# RemSw1_0.net
KiCad netlist of a schematic drawn in EAGLE
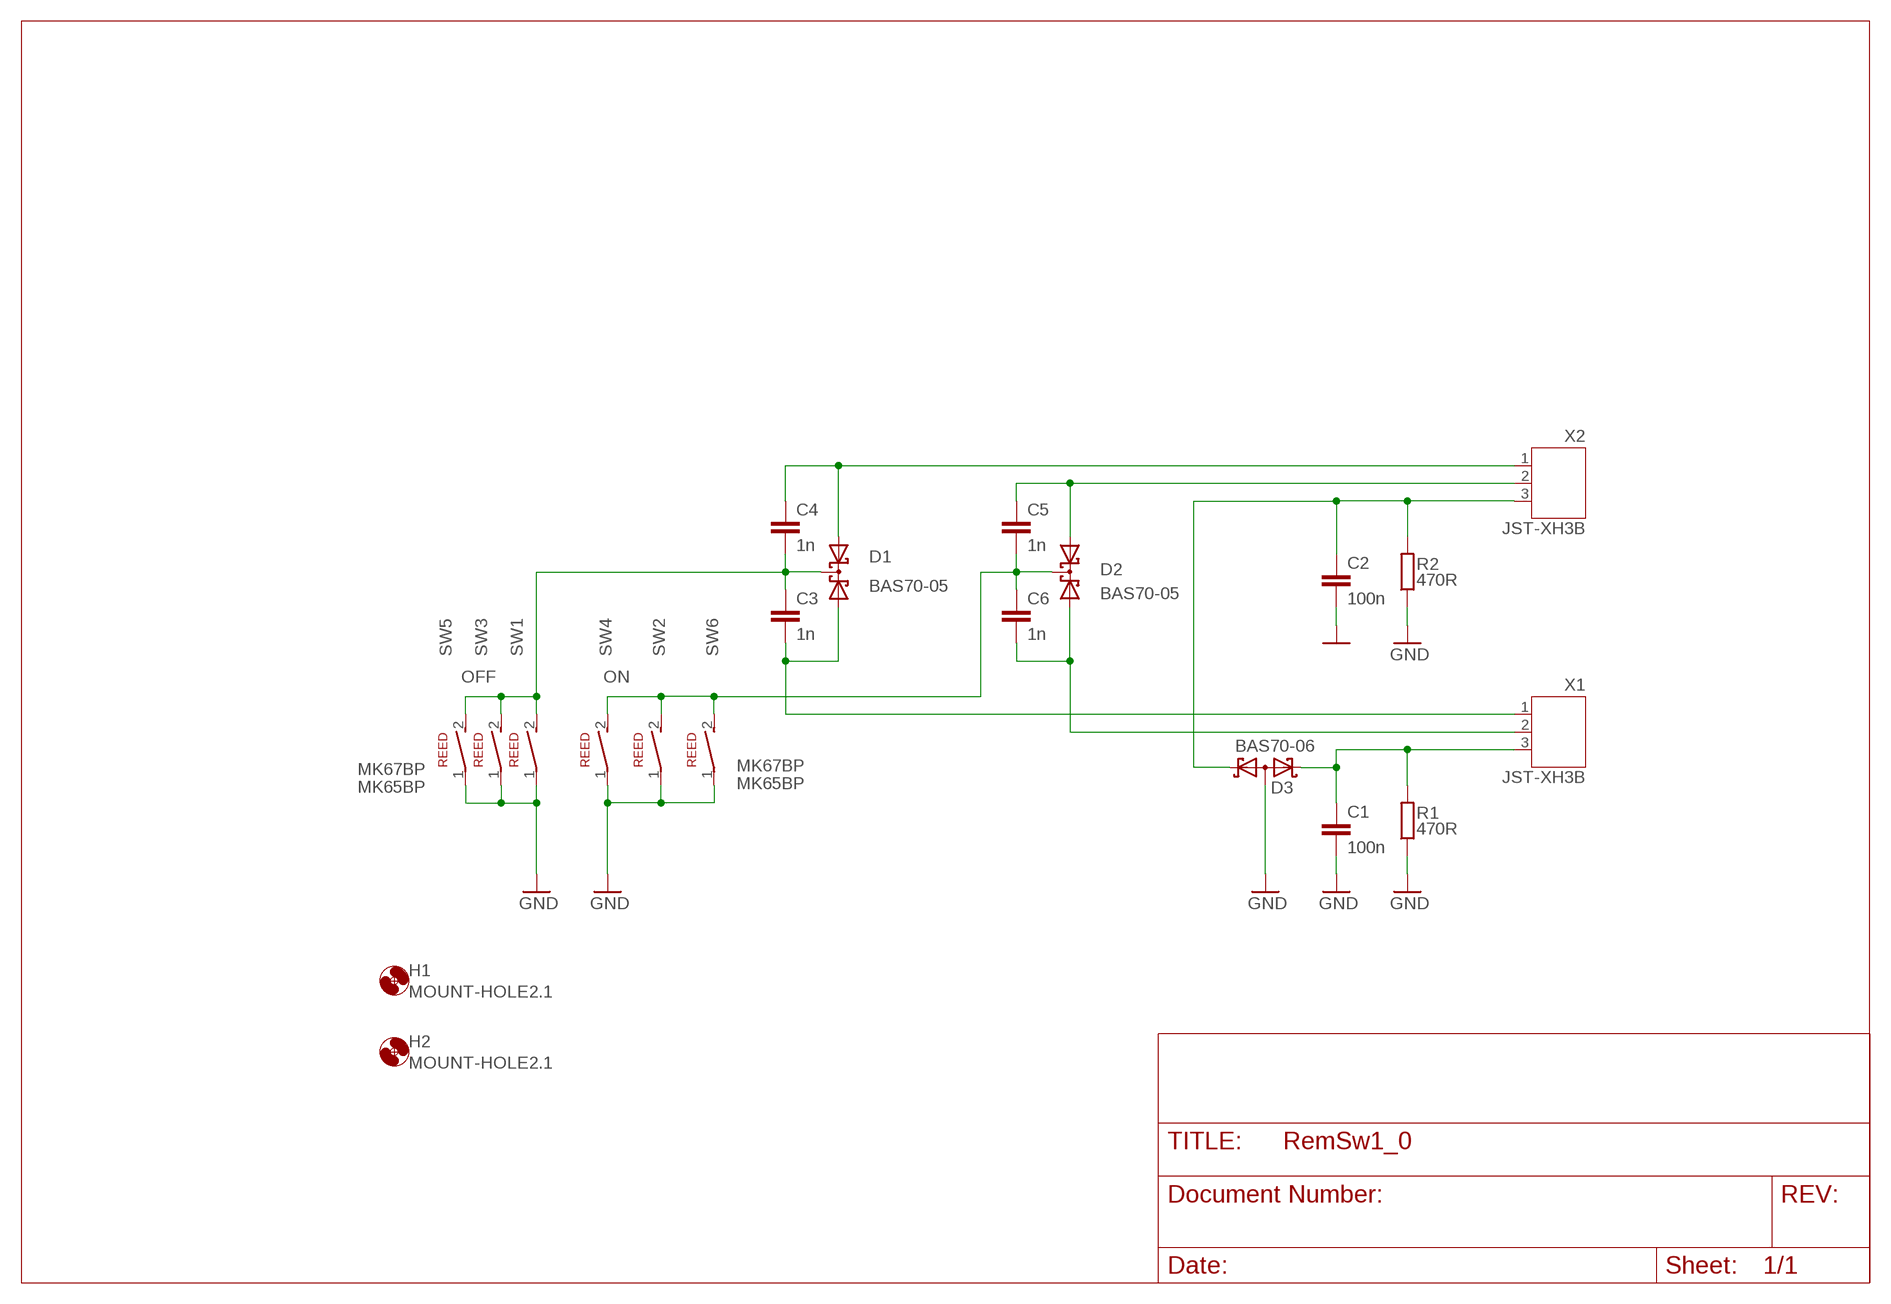
[diagram p0: schematic, sheet 1]

(export (version "E")
  (design (tool "Eeschema 10.0.6"))
  (components
    (comp (ref "C1")
      (value "100n")
      (footprint "eagle-import:C0805")
      (libsource (lib "eagle-import") (part "C-EUC0805"))
    )
    (comp (ref "C2")
      (value "100n")
      (footprint "eagle-import:C0805")
      (libsource (lib "eagle-import") (part "C-EUC0805"))
    )
    (comp (ref "C3")
      (value "1n")
      (footprint "eagle-import:C0805")
      (libsource (lib "eagle-import") (part "C-EUC0805"))
    )
    (comp (ref "C4")
      (value "1n")
      (footprint "eagle-import:C0805")
      (libsource (lib "eagle-import") (part "C-EUC0805"))
    )
    (comp (ref "C5")
      (value "1n")
      (footprint "eagle-import:C0805")
      (libsource (lib "eagle-import") (part "C-EUC0805"))
    )
    (comp (ref "C6")
      (value "1n")
      (footprint "eagle-import:C0805")
      (libsource (lib "eagle-import") (part "C-EUC0805"))
    )
    (comp (ref "D1")
      (value "BAS70-05")
      (footprint "eagle-import:SOT23")
      (libsource (lib "eagle-import") (part "BAS70-05"))
    )
    (comp (ref "D2")
      (value "BAS70-05")
      (footprint "eagle-import:SOT23")
      (libsource (lib "eagle-import") (part "BAS70-05"))
    )
    (comp (ref "D3")
      (value "BAS70-06")
      (footprint "eagle-import:SOT23")
      (libsource (lib "eagle-import") (part "BAS70-06"))
    )
    (comp (ref "H1")
      (value "MOUNT-HOLE2.1")
      (footprint "eagle-import:2,1")
      (libsource (lib "eagle-import") (part "MOUNT-HOLE2.1"))
    )
    (comp (ref "H2")
      (value "MOUNT-HOLE2.1")
      (footprint "eagle-import:2,1")
      (libsource (lib "eagle-import") (part "MOUNT-HOLE2.1"))
    )
    (comp (ref "R1")
      (value "470R")
      (footprint "eagle-import:R0805")
      (libsource (lib "eagle-import") (part "R-EU_R0805"))
    )
    (comp (ref "R2")
      (value "470R")
      (footprint "eagle-import:R0805")
      (libsource (lib "eagle-import") (part "R-EU_R0805"))
    )
    (comp (ref "SW1")
      (value "OFF")
      (footprint "eagle-import:KSK1A66")
      (libsource (lib "eagle-import") (part "KSK1A66"))
    )
    (comp (ref "SW2")
      (value "ON")
      (footprint "eagle-import:KSK1A66")
      (libsource (lib "eagle-import") (part "KSK1A66"))
    )
    (comp (ref "SW3")
      (value "MK67BP")
      (footprint "eagle-import:MK67-BP")
      (libsource (lib "eagle-import") (part "MK67BP"))
    )
    (comp (ref "SW4")
      (value "MK65BP")
      (footprint "eagle-import:MK65-BP")
      (libsource (lib "eagle-import") (part "MK65BP"))
    )
    (comp (ref "SW5")
      (value "MK65BP")
      (footprint "eagle-import:MK65-BP")
      (libsource (lib "eagle-import") (part "MK65BP"))
    )
    (comp (ref "SW6")
      (value "MK67BP")
      (footprint "eagle-import:MK67-BP")
      (libsource (lib "eagle-import") (part "MK67BP"))
    )
    (comp (ref "X1")
      (value "JST-XH3B")
      (footprint "eagle-import:B3B-XH")
      (libsource (lib "eagle-import") (part "JST-XH3B"))
    )
    (comp (ref "X2")
      (value "JST-XH3B")
      (footprint "eagle-import:B3B-XH")
      (libsource (lib "eagle-import") (part "JST-XH3B"))
    )
  )
  (nets
    (net (code "1") (name "GND") (class "Default")
      (node (ref "C1") (pin "2") (pinfunction "2_2") (pintype "passive"))
      (node (ref "C2") (pin "2") (pinfunction "2_2") (pintype "passive"))
      (node (ref "D3") (pin "3") (pinfunction "AA_3") (pintype "passive"))
      (node (ref "R1") (pin "1") (pinfunction "1_1") (pintype "passive"))
      (node (ref "R2") (pin "1") (pinfunction "1_1") (pintype "passive"))
      (node (ref "SW1") (pin "1") (pinfunction "1_1") (pintype "passive"))
      (node (ref "SW2") (pin "1") (pinfunction "1_1") (pintype "passive"))
      (node (ref "SW3") (pin "1") (pinfunction "1_1") (pintype "passive"))
      (node (ref "SW4") (pin "1") (pinfunction "1_1") (pintype "passive"))
      (node (ref "SW5") (pin "1") (pinfunction "1_1") (pintype "passive"))
      (node (ref "SW6") (pin "1") (pinfunction "1_1") (pintype "passive"))
    )
    (net (code "2") (name "Net-(D1-A1)") (class "Default")
      (node (ref "C3") (pin "2") (pinfunction "2_2") (pintype "passive"))
      (node (ref "D1") (pin "1") (pinfunction "A1_1") (pintype "passive"))
      (node (ref "X1") (pin "1") (pinfunction "1_1") (pintype "passive"))
    )
    (net (code "3") (name "Net-(D1-A2)") (class "Default")
      (node (ref "C4") (pin "1") (pinfunction "1_1") (pintype "passive"))
      (node (ref "D1") (pin "2") (pinfunction "A2_2") (pintype "passive"))
      (node (ref "X2") (pin "1") (pinfunction "1_1") (pintype "passive"))
    )
    (net (code "4") (name "Net-(D1-C)") (class "Default")
      (node (ref "C3") (pin "1") (pinfunction "1_1") (pintype "passive"))
      (node (ref "C4") (pin "2") (pinfunction "2_2") (pintype "passive"))
      (node (ref "D1") (pin "3") (pinfunction "C_3") (pintype "passive"))
      (node (ref "SW1") (pin "2") (pinfunction "2_2") (pintype "passive"))
      (node (ref "SW3") (pin "2") (pinfunction "2_2") (pintype "passive"))
      (node (ref "SW5") (pin "2") (pinfunction "2_2") (pintype "passive"))
    )
    (net (code "5") (name "Net-(D2-A1)") (class "Default")
      (node (ref "C5") (pin "1") (pinfunction "1_1") (pintype "passive"))
      (node (ref "D2") (pin "1") (pinfunction "A1_1") (pintype "passive"))
      (node (ref "X2") (pin "2") (pinfunction "2_2") (pintype "passive"))
    )
    (net (code "6") (name "Net-(D2-A2)") (class "Default")
      (node (ref "C6") (pin "2") (pinfunction "2_2") (pintype "passive"))
      (node (ref "D2") (pin "2") (pinfunction "A2_2") (pintype "passive"))
      (node (ref "X1") (pin "2") (pinfunction "2_2") (pintype "passive"))
    )
    (net (code "7") (name "Net-(D2-C)") (class "Default")
      (node (ref "C5") (pin "2") (pinfunction "2_2") (pintype "passive"))
      (node (ref "C6") (pin "1") (pinfunction "1_1") (pintype "passive"))
      (node (ref "D2") (pin "3") (pinfunction "C_3") (pintype "passive"))
      (node (ref "SW2") (pin "2") (pinfunction "2_2") (pintype "passive"))
      (node (ref "SW4") (pin "2") (pinfunction "2_2") (pintype "passive"))
      (node (ref "SW6") (pin "2") (pinfunction "2_2") (pintype "passive"))
    )
    (net (code "8") (name "Net-(D3-K1)") (class "Default")
      (node (ref "C2") (pin "1") (pinfunction "1_1") (pintype "passive"))
      (node (ref "D3") (pin "1") (pinfunction "K1_1") (pintype "passive"))
      (node (ref "R2") (pin "2") (pinfunction "2_2") (pintype "passive"))
      (node (ref "X2") (pin "3") (pinfunction "3_3") (pintype "passive"))
    )
    (net (code "9") (name "Net-(D3-K2)") (class "Default")
      (node (ref "C1") (pin "1") (pinfunction "1_1") (pintype "passive"))
      (node (ref "D3") (pin "2") (pinfunction "K2_2") (pintype "passive"))
      (node (ref "R1") (pin "2") (pinfunction "2_2") (pintype "passive"))
      (node (ref "X1") (pin "3") (pinfunction "3_3") (pintype "passive"))
    )
  )
)
